# bias_v1.net
KiCad netlist of a schematic drawn in EAGLE
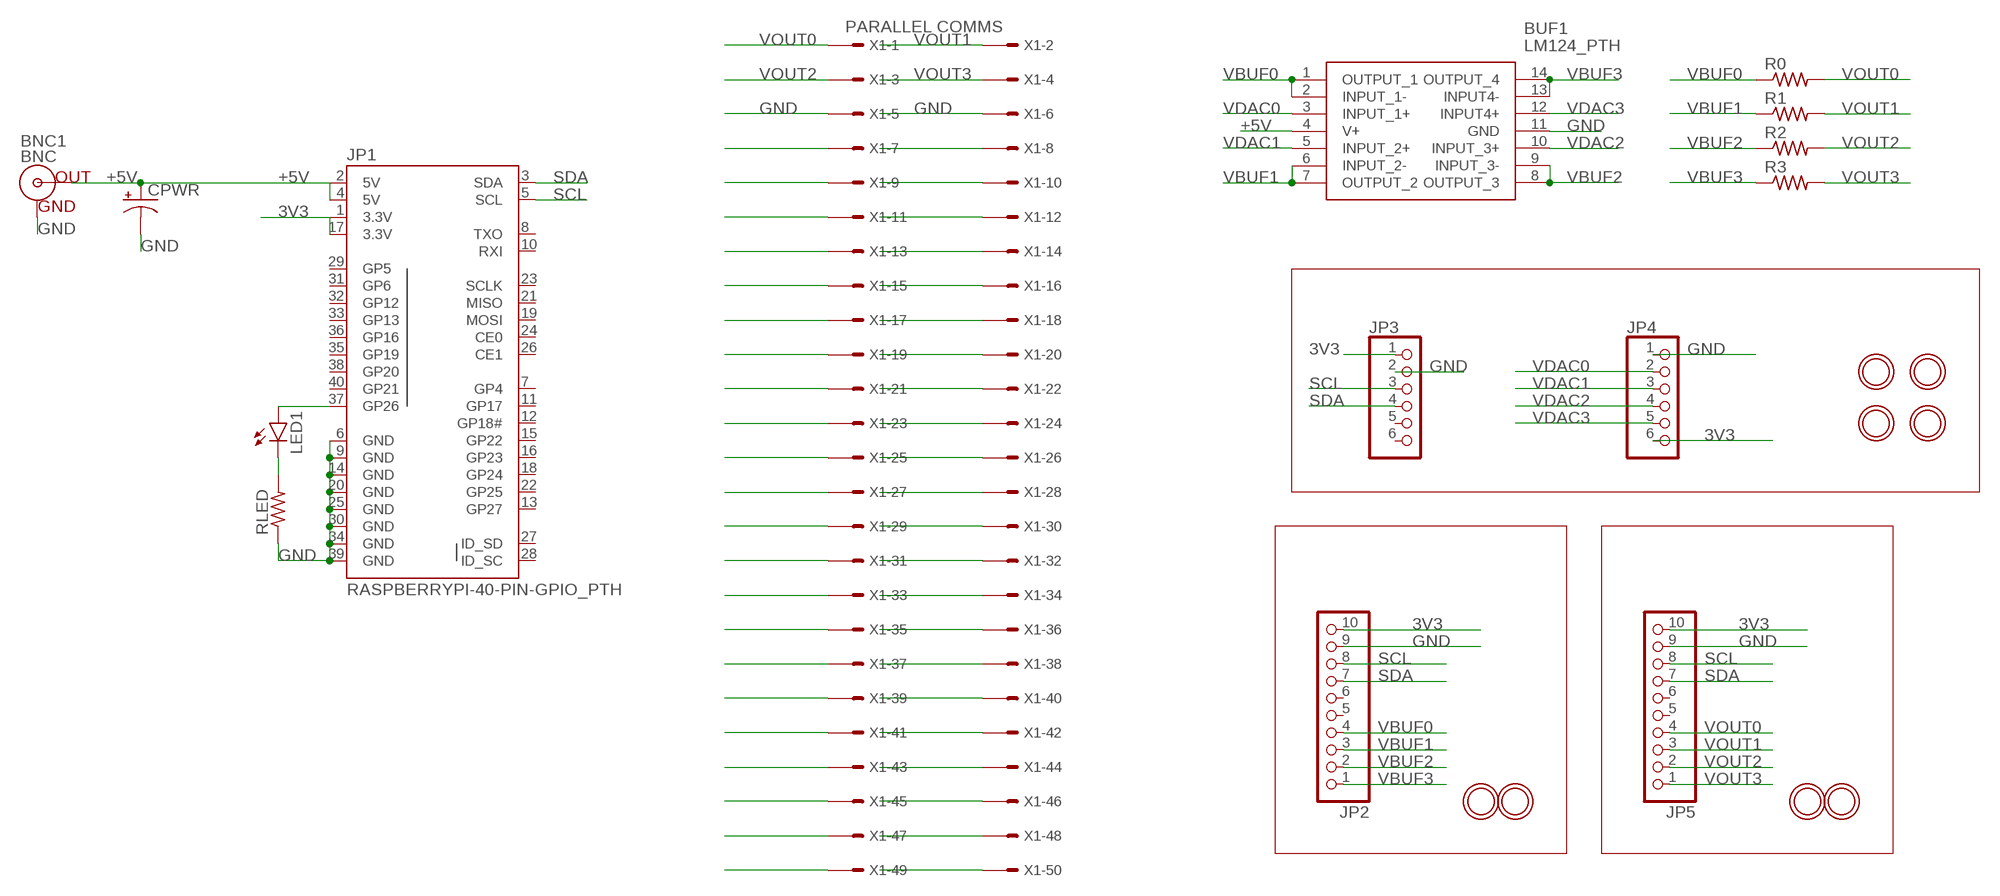
[diagram p0: schematic, sheet 1]

(export (version "E")
  (design (tool "Eeschema 10.0.6"))
  (components
    (comp (ref "BNC1")
      (value "BNC")
      (footprint "eagle-import:BNC")
      (libsource (lib "eagle-import") (part "BNCPTH"))
    )
    (comp (ref "BUF1")
      (value "LM124_PTH")
      (footprint "eagle-import:CDIP790W66P254L1954H508Q14")
      (fields (field (name "ARROW_PART_NUMBER") "LM124J/PB") (field (name "MOUSER_PART_NUMBER") "926-LM124J"))
      (libsource (lib "eagle-import") (part "LM124_PTH"))
    )
    (comp (ref "CPWR")
      (value "CPOL-USE2.5-6")
      (footprint "eagle-import:E2,5-6")
      (libsource (lib "eagle-import") (part "CPOL-USE2.5-6"))
    )
    (comp (ref "JP1")
      (value "RASPBERRYPI-40-PIN-GPIO_PTH")
      (footprint "eagle-import:2X20_SHROUDED")
      (libsource (lib "eagle-import") (part "RASPBERRYPI-40-PIN-GPIO_PTH"))
    )
    (comp (ref "JP2")
      (value "HEADER-1X1070MIL")
      (footprint "eagle-import:1X10_ROUND70")
      (libsource (lib "eagle-import") (part "HEADER-1X1070MIL"))
    )
    (comp (ref "JP3")
      (value "HEADER-1X670MIL")
      (footprint "eagle-import:1X06_ROUND_70")
      (libsource (lib "eagle-import") (part "HEADER-1X670MIL"))
    )
    (comp (ref "JP4")
      (value "HEADER-1X670MIL")
      (footprint "eagle-import:1X06_ROUND_70")
      (libsource (lib "eagle-import") (part "HEADER-1X670MIL"))
    )
    (comp (ref "JP5")
      (value "HEADER-1X1070MIL")
      (footprint "eagle-import:1X10_ROUND70")
      (libsource (lib "eagle-import") (part "HEADER-1X1070MIL"))
    )
    (comp (ref "LED1")
      (value "LED3MM")
      (footprint "eagle-import:LED3MM")
      (libsource (lib "eagle-import") (part "LED3MM"))
    )
    (comp (ref "R0")
      (value "R-US_0204/7")
      (footprint "eagle-import:0204_7")
      (libsource (lib "eagle-import") (part "R-US_0204/7"))
    )
    (comp (ref "R1")
      (value "R-US_0204/7")
      (footprint "eagle-import:0204_7")
      (libsource (lib "eagle-import") (part "R-US_0204/7"))
    )
    (comp (ref "R2")
      (value "R-US_0204/7")
      (footprint "eagle-import:0204_7")
      (libsource (lib "eagle-import") (part "R-US_0204/7"))
    )
    (comp (ref "R3")
      (value "R-US_0204/7")
      (footprint "eagle-import:0204_7")
      (libsource (lib "eagle-import") (part "R-US_0204/7"))
    )
    (comp (ref "RLED")
      (value "R-US_0204/7")
      (footprint "eagle-import:0204_7")
      (libsource (lib "eagle-import") (part "R-US_0204/7"))
    )
    (comp (ref "U$3")
      (value "MOUNTINGHOLE2.5")
      (footprint "eagle-import:MOUNTINGHOLE_2.5_PLATED")
      (libsource (lib "eagle-import") (part "MOUNTINGHOLE2.5"))
    )
    (comp (ref "U$4")
      (value "MOUNTINGHOLE2.5")
      (footprint "eagle-import:MOUNTINGHOLE_2.5_PLATED")
      (libsource (lib "eagle-import") (part "MOUNTINGHOLE2.5"))
    )
    (comp (ref "U$5")
      (value "MOUNTINGHOLE2.5")
      (footprint "eagle-import:MOUNTINGHOLE_2.5_PLATED")
      (libsource (lib "eagle-import") (part "MOUNTINGHOLE2.5"))
    )
    (comp (ref "U$6")
      (value "MOUNTINGHOLE2.5")
      (footprint "eagle-import:MOUNTINGHOLE_2.5_PLATED")
      (libsource (lib "eagle-import") (part "MOUNTINGHOLE2.5"))
    )
    (comp (ref "U$7")
      (value "MOUNTINGHOLE2.5")
      (footprint "eagle-import:MOUNTINGHOLE_2.5_PLATED")
      (libsource (lib "eagle-import") (part "MOUNTINGHOLE2.5"))
    )
    (comp (ref "U$8")
      (value "MOUNTINGHOLE2.5")
      (footprint "eagle-import:MOUNTINGHOLE_2.5_PLATED")
      (libsource (lib "eagle-import") (part "MOUNTINGHOLE2.5"))
    )
    (comp (ref "U$15")
      (value "MOUNTINGHOLE2.5")
      (footprint "eagle-import:MOUNTINGHOLE_2.5_PLATED")
      (libsource (lib "eagle-import") (part "MOUNTINGHOLE2.5"))
    )
    (comp (ref "U$16")
      (value "MOUNTINGHOLE2.5")
      (footprint "eagle-import:MOUNTINGHOLE_2.5_PLATED")
      (libsource (lib "eagle-import") (part "MOUNTINGHOLE2.5"))
    )
    (comp (ref "X1")
      (value "PARALLEL COMMS")
      (footprint "eagle-import:057-050-1")
      (libsource (lib "eagle-import") (part "057-050-1"))
    )
  )
  (nets
    (net (code "1") (name "/+5V") (class "Default")
      (node (ref "BNC1") (pin "S") (pinfunction "OUT_S") (pintype "bidirectional"))
      (node (ref "BUF1") (pin "4") (pinfunction "V+_4") (pintype "bidirectional"))
      (node (ref "CPWR") (pin "+") (pinfunction "+_+") (pintype "passive"))
      (node (ref "JP1") (pin "2") (pinfunction "5V_2") (pintype "power_in"))
      (node (ref "JP1") (pin "4") (pinfunction "5V_4") (pintype "power_in"))
    )
    (net (code "2") (name "/3V3") (class "Default")
      (node (ref "JP1") (pin "1") (pinfunction "3.3V_1") (pintype "power_in"))
      (node (ref "JP1") (pin "17") (pinfunction "3.3V_17") (pintype "power_in"))
      (node (ref "JP2") (pin "10") (pinfunction "10_10") (pintype "passive"))
      (node (ref "JP3") (pin "1") (pinfunction "1_1") (pintype "passive"))
      (node (ref "JP4") (pin "6") (pinfunction "6_6") (pintype "passive"))
      (node (ref "JP5") (pin "10") (pinfunction "10_10") (pintype "passive"))
    )
    (net (code "3") (name "/GND") (class "Default")
      (node (ref "BNC1") (pin "GND") (pinfunction "GND_GND") (pintype "bidirectional"))
      (node (ref "BUF1") (pin "11") (pinfunction "GND_11") (pintype "bidirectional"))
      (node (ref "CPWR") (pin "-") (pinfunction "-_-") (pintype "passive"))
      (node (ref "JP1") (pin "14") (pinfunction "GND_14") (pintype "power_in"))
      (node (ref "JP1") (pin "20") (pinfunction "GND_20") (pintype "power_in"))
      (node (ref "JP1") (pin "25") (pinfunction "GND_25") (pintype "power_in"))
      (node (ref "JP1") (pin "30") (pinfunction "GND_30") (pintype "power_in"))
      (node (ref "JP1") (pin "34") (pinfunction "GND_34") (pintype "power_in"))
      (node (ref "JP1") (pin "39") (pinfunction "GND_39") (pintype "power_in"))
      (node (ref "JP1") (pin "6") (pinfunction "GND_6") (pintype "power_in"))
      (node (ref "JP1") (pin "9") (pinfunction "GND_9") (pintype "power_in"))
      (node (ref "JP2") (pin "9") (pinfunction "9_9") (pintype "passive"))
      (node (ref "JP3") (pin "2") (pinfunction "2_2") (pintype "passive"))
      (node (ref "JP4") (pin "1") (pinfunction "1_1") (pintype "passive"))
      (node (ref "JP5") (pin "9") (pinfunction "9_9") (pintype "passive"))
      (node (ref "RLED") (pin "1") (pinfunction "1_1") (pintype "passive"))
      (node (ref "X1") (pin "5") (pinfunction "S_5") (pintype "passive"))
      (node (ref "X1") (pin "6") (pinfunction "S_6") (pintype "passive"))
    )
    (net (code "4") (name "/SCL") (class "Default")
      (node (ref "JP1") (pin "5") (pinfunction "SCL_5") (pintype "bidirectional"))
      (node (ref "JP2") (pin "8") (pinfunction "8_8") (pintype "passive"))
      (node (ref "JP3") (pin "3") (pinfunction "3_3") (pintype "passive"))
      (node (ref "JP5") (pin "8") (pinfunction "8_8") (pintype "passive"))
    )
    (net (code "5") (name "/SDA") (class "Default")
      (node (ref "JP1") (pin "3") (pinfunction "SDA_3") (pintype "bidirectional"))
      (node (ref "JP2") (pin "7") (pinfunction "7_7") (pintype "passive"))
      (node (ref "JP3") (pin "4") (pinfunction "4_4") (pintype "passive"))
      (node (ref "JP5") (pin "7") (pinfunction "7_7") (pintype "passive"))
    )
    (net (code "6") (name "/VBUF0") (class "Default")
      (node (ref "BUF1") (pin "1") (pinfunction "OUTPUT_1_1") (pintype "bidirectional"))
      (node (ref "BUF1") (pin "2") (pinfunction "INPUT_1-_2") (pintype "bidirectional"))
      (node (ref "JP2") (pin "4") (pinfunction "4_4") (pintype "passive"))
      (node (ref "R0") (pin "1") (pinfunction "1_1") (pintype "passive"))
    )
    (net (code "7") (name "/VBUF1") (class "Default")
      (node (ref "BUF1") (pin "6") (pinfunction "INPUT_2-_6") (pintype "bidirectional"))
      (node (ref "BUF1") (pin "7") (pinfunction "OUTPUT_2_7") (pintype "bidirectional"))
      (node (ref "JP2") (pin "3") (pinfunction "3_3") (pintype "passive"))
      (node (ref "R1") (pin "1") (pinfunction "1_1") (pintype "passive"))
    )
    (net (code "8") (name "/VBUF2") (class "Default")
      (node (ref "BUF1") (pin "8") (pinfunction "OUTPUT_3_8") (pintype "bidirectional"))
      (node (ref "BUF1") (pin "9") (pinfunction "INPUT_3-_9") (pintype "bidirectional"))
      (node (ref "JP2") (pin "2") (pinfunction "2_2") (pintype "passive"))
      (node (ref "R2") (pin "1") (pinfunction "1_1") (pintype "passive"))
    )
    (net (code "9") (name "/VBUF3") (class "Default")
      (node (ref "BUF1") (pin "13") (pinfunction "INPUT4-_13") (pintype "bidirectional"))
      (node (ref "BUF1") (pin "14") (pinfunction "OUTPUT_4_14") (pintype "bidirectional"))
      (node (ref "JP2") (pin "1") (pinfunction "1_1") (pintype "passive"))
      (node (ref "R3") (pin "1") (pinfunction "1_1") (pintype "passive"))
    )
    (net (code "10") (name "/VDAC0") (class "Default")
      (node (ref "BUF1") (pin "3") (pinfunction "INPUT_1+_3") (pintype "bidirectional"))
      (node (ref "JP4") (pin "2") (pinfunction "2_2") (pintype "passive"))
    )
    (net (code "11") (name "/VDAC1") (class "Default")
      (node (ref "BUF1") (pin "5") (pinfunction "INPUT_2+_5") (pintype "bidirectional"))
      (node (ref "JP4") (pin "3") (pinfunction "3_3") (pintype "passive"))
    )
    (net (code "12") (name "/VDAC2") (class "Default")
      (node (ref "BUF1") (pin "10") (pinfunction "INPUT_3+_10") (pintype "bidirectional"))
      (node (ref "JP4") (pin "4") (pinfunction "4_4") (pintype "passive"))
    )
    (net (code "13") (name "/VDAC3") (class "Default")
      (node (ref "BUF1") (pin "12") (pinfunction "INPUT4+_12") (pintype "bidirectional"))
      (node (ref "JP4") (pin "5") (pinfunction "5_5") (pintype "passive"))
    )
    (net (code "14") (name "/VOUT0") (class "Default")
      (node (ref "JP5") (pin "4") (pinfunction "4_4") (pintype "passive"))
      (node (ref "R0") (pin "2") (pinfunction "2_2") (pintype "passive"))
      (node (ref "X1") (pin "1") (pinfunction "S_1") (pintype "passive"))
    )
    (net (code "15") (name "/VOUT1") (class "Default")
      (node (ref "JP5") (pin "3") (pinfunction "3_3") (pintype "passive"))
      (node (ref "R1") (pin "2") (pinfunction "2_2") (pintype "passive"))
      (node (ref "X1") (pin "2") (pinfunction "S_2") (pintype "passive"))
    )
    (net (code "16") (name "/VOUT2") (class "Default")
      (node (ref "JP5") (pin "2") (pinfunction "2_2") (pintype "passive"))
      (node (ref "R2") (pin "2") (pinfunction "2_2") (pintype "passive"))
      (node (ref "X1") (pin "3") (pinfunction "S_3") (pintype "passive"))
    )
    (net (code "17") (name "/VOUT3") (class "Default")
      (node (ref "JP5") (pin "1") (pinfunction "1_1") (pintype "passive"))
      (node (ref "R3") (pin "2") (pinfunction "2_2") (pintype "passive"))
      (node (ref "X1") (pin "4") (pinfunction "S_4") (pintype "passive"))
    )
    (net (code "18") (name "Net-(JP1-GP26)") (class "Default")
      (node (ref "JP1") (pin "37") (pinfunction "GP26_37") (pintype "bidirectional"))
      (node (ref "LED1") (pin "A") (pinfunction "A_A") (pintype "passive"))
    )
    (net (code "19") (name "Net-(LED1-C)") (class "Default")
      (node (ref "LED1") (pin "K") (pinfunction "C_K") (pintype "passive"))
      (node (ref "RLED") (pin "2") (pinfunction "2_2") (pintype "passive"))
    )
    (net (code "20") (name "unconnected-(JP1-CE0-Pad24)") (class "Default")
      (node (ref "JP1") (pin "24") (pinfunction "CE0_24") (pintype "output"))
    )
    (net (code "21") (name "unconnected-(JP1-CE1-Pad26)") (class "Default")
      (node (ref "JP1") (pin "26") (pinfunction "CE1_26") (pintype "output"))
    )
    (net (code "22") (name "unconnected-(JP1-GP4-Pad7)") (class "Default")
      (node (ref "JP1") (pin "7") (pinfunction "GP4_7") (pintype "bidirectional"))
    )
    (net (code "23") (name "unconnected-(JP1-GP5-Pad29)") (class "Default")
      (node (ref "JP1") (pin "29") (pinfunction "GP5_29") (pintype "bidirectional"))
    )
    (net (code "24") (name "unconnected-(JP1-GP6-Pad31)") (class "Default")
      (node (ref "JP1") (pin "31") (pinfunction "GP6_31") (pintype "bidirectional"))
    )
    (net (code "25") (name "unconnected-(JP1-GP12-Pad32)") (class "Default")
      (node (ref "JP1") (pin "32") (pinfunction "GP12_32") (pintype "bidirectional"))
    )
    (net (code "26") (name "unconnected-(JP1-GP13-Pad33)") (class "Default")
      (node (ref "JP1") (pin "33") (pinfunction "GP13_33") (pintype "bidirectional"))
    )
    (net (code "27") (name "unconnected-(JP1-GP16-Pad36)") (class "Default")
      (node (ref "JP1") (pin "36") (pinfunction "GP16_36") (pintype "bidirectional"))
    )
    (net (code "28") (name "unconnected-(JP1-GP17-Pad11)") (class "Default")
      (node (ref "JP1") (pin "11") (pinfunction "GP17_11") (pintype "bidirectional"))
    )
    (net (code "29") (name "unconnected-(JP1-GP18#-Pad12)") (class "Default")
      (node (ref "JP1") (pin "12") (pinfunction "GP18#_12") (pintype "bidirectional"))
    )
    (net (code "30") (name "unconnected-(JP1-GP19-Pad35)") (class "Default")
      (node (ref "JP1") (pin "35") (pinfunction "GP19_35") (pintype "bidirectional"))
    )
    (net (code "31") (name "unconnected-(JP1-GP20-Pad38)") (class "Default")
      (node (ref "JP1") (pin "38") (pinfunction "GP20_38") (pintype "bidirectional"))
    )
    (net (code "32") (name "unconnected-(JP1-GP21-Pad40)") (class "Default")
      (node (ref "JP1") (pin "40") (pinfunction "GP21_40") (pintype "bidirectional"))
    )
    (net (code "33") (name "unconnected-(JP1-GP22-Pad15)") (class "Default")
      (node (ref "JP1") (pin "15") (pinfunction "GP22_15") (pintype "bidirectional"))
    )
    (net (code "34") (name "unconnected-(JP1-GP23-Pad16)") (class "Default")
      (node (ref "JP1") (pin "16") (pinfunction "GP23_16") (pintype "bidirectional"))
    )
    (net (code "35") (name "unconnected-(JP1-GP24-Pad18)") (class "Default")
      (node (ref "JP1") (pin "18") (pinfunction "GP24_18") (pintype "bidirectional"))
    )
    (net (code "36") (name "unconnected-(JP1-GP25-Pad22)") (class "Default")
      (node (ref "JP1") (pin "22") (pinfunction "GP25_22") (pintype "bidirectional"))
    )
    (net (code "37") (name "unconnected-(JP1-GP27-Pad13)") (class "Default")
      (node (ref "JP1") (pin "13") (pinfunction "GP27_13") (pintype "bidirectional"))
    )
    (net (code "38") (name "unconnected-(JP1-ID_SC-Pad28)") (class "Default")
      (node (ref "JP1") (pin "28") (pinfunction "ID_SC_28") (pintype "bidirectional"))
    )
    (net (code "39") (name "unconnected-(JP1-ID_SD-Pad27)") (class "Default")
      (node (ref "JP1") (pin "27") (pinfunction "ID_SD_27") (pintype "bidirectional"))
    )
    (net (code "40") (name "unconnected-(JP1-MISO-Pad21)") (class "Default")
      (node (ref "JP1") (pin "21") (pinfunction "MISO_21") (pintype "input"))
    )
    (net (code "41") (name "unconnected-(JP1-MOSI-Pad19)") (class "Default")
      (node (ref "JP1") (pin "19") (pinfunction "MOSI_19") (pintype "output"))
    )
    (net (code "42") (name "unconnected-(JP1-RXI-Pad10)") (class "Default")
      (node (ref "JP1") (pin "10") (pinfunction "RXI_10") (pintype "input"))
    )
    (net (code "43") (name "unconnected-(JP1-SCLK-Pad23)") (class "Default")
      (node (ref "JP1") (pin "23") (pinfunction "SCLK_23") (pintype "output"))
    )
    (net (code "44") (name "unconnected-(JP1-TXO-Pad8)") (class "Default")
      (node (ref "JP1") (pin "8") (pinfunction "TXO_8") (pintype "output"))
    )
    (net (code "45") (name "unconnected-(JP2-Pad5)") (class "Default")
      (node (ref "JP2") (pin "5") (pinfunction "5_5") (pintype "passive"))
    )
    (net (code "46") (name "unconnected-(JP2-Pad6)") (class "Default")
      (node (ref "JP2") (pin "6") (pinfunction "6_6") (pintype "passive"))
    )
    (net (code "47") (name "unconnected-(JP3-Pad5)") (class "Default")
      (node (ref "JP3") (pin "5") (pinfunction "5_5") (pintype "passive"))
    )
    (net (code "48") (name "unconnected-(JP3-Pad6)") (class "Default")
      (node (ref "JP3") (pin "6") (pinfunction "6_6") (pintype "passive"))
    )
    (net (code "49") (name "unconnected-(JP5-Pad5)") (class "Default")
      (node (ref "JP5") (pin "5") (pinfunction "5_5") (pintype "passive"))
    )
    (net (code "50") (name "unconnected-(JP5-Pad6)") (class "Default")
      (node (ref "JP5") (pin "6") (pinfunction "6_6") (pintype "passive"))
    )
    (net (code "51") (name "unconnected-(X1AA-S-Pad33)") (class "Default")
      (node (ref "X1") (pin "33") (pinfunction "S_33") (pintype "passive"))
    )
    (net (code "52") (name "unconnected-(X1AB-S-Pad34)") (class "Default")
      (node (ref "X1") (pin "34") (pinfunction "S_34") (pintype "passive"))
    )
    (net (code "53") (name "unconnected-(X1AC-S-Pad35)") (class "Default")
      (node (ref "X1") (pin "35") (pinfunction "S_35") (pintype "passive"))
    )
    (net (code "54") (name "unconnected-(X1AD-S-Pad36)") (class "Default")
      (node (ref "X1") (pin "36") (pinfunction "S_36") (pintype "passive"))
    )
    (net (code "55") (name "unconnected-(X1AE-S-Pad37)") (class "Default")
      (node (ref "X1") (pin "37") (pinfunction "S_37") (pintype "passive"))
    )
    (net (code "56") (name "unconnected-(X1AF-S-Pad38)") (class "Default")
      (node (ref "X1") (pin "38") (pinfunction "S_38") (pintype "passive"))
    )
    (net (code "57") (name "unconnected-(X1AG-S-Pad39)") (class "Default")
      (node (ref "X1") (pin "39") (pinfunction "S_39") (pintype "passive"))
    )
    (net (code "58") (name "unconnected-(X1AI-S-Pad40)") (class "Default")
      (node (ref "X1") (pin "40") (pinfunction "S_40") (pintype "passive"))
    )
    (net (code "59") (name "unconnected-(X1AJ-S-Pad41)") (class "Default")
      (node (ref "X1") (pin "41") (pinfunction "S_41") (pintype "passive"))
    )
    (net (code "60") (name "unconnected-(X1AK-S-Pad42)") (class "Default")
      (node (ref "X1") (pin "42") (pinfunction "S_42") (pintype "passive"))
    )
    (net (code "61") (name "unconnected-(X1AL-S-Pad43)") (class "Default")
      (node (ref "X1") (pin "43") (pinfunction "S_43") (pintype "passive"))
    )
    (net (code "62") (name "unconnected-(X1AM-S-Pad44)") (class "Default")
      (node (ref "X1") (pin "44") (pinfunction "S_44") (pintype "passive"))
    )
    (net (code "63") (name "unconnected-(X1AN-S-Pad45)") (class "Default")
      (node (ref "X1") (pin "45") (pinfunction "S_45") (pintype "passive"))
    )
    (net (code "64") (name "unconnected-(X1AO-S-Pad46)") (class "Default")
      (node (ref "X1") (pin "46") (pinfunction "S_46") (pintype "passive"))
    )
    (net (code "65") (name "unconnected-(X1AP-S-Pad47)") (class "Default")
      (node (ref "X1") (pin "47") (pinfunction "S_47") (pintype "passive"))
    )
    (net (code "66") (name "unconnected-(X1AQ-S-Pad48)") (class "Default")
      (node (ref "X1") (pin "48") (pinfunction "S_48") (pintype "passive"))
    )
    (net (code "67") (name "unconnected-(X1AR-S-Pad49)") (class "Default")
      (node (ref "X1") (pin "49") (pinfunction "S_49") (pintype "passive"))
    )
    (net (code "68") (name "unconnected-(X1AT-S-Pad50)") (class "Default")
      (node (ref "X1") (pin "50") (pinfunction "S_50") (pintype "passive"))
    )
    (net (code "69") (name "unconnected-(X1AV-S-Pad7)") (class "Default")
      (node (ref "X1") (pin "7") (pinfunction "S_7") (pintype "passive"))
    )
    (net (code "70") (name "unconnected-(X1AW-S-Pad8)") (class "Default")
      (node (ref "X1") (pin "8") (pinfunction "S_8") (pintype "passive"))
    )
    (net (code "71") (name "unconnected-(X1AX-S-Pad9)") (class "Default")
      (node (ref "X1") (pin "9") (pinfunction "S_9") (pintype "passive"))
    )
    (net (code "72") (name "unconnected-(X1B-S-Pad10)") (class "Default")
      (node (ref "X1") (pin "10") (pinfunction "S_10") (pintype "passive"))
    )
    (net (code "73") (name "unconnected-(X1C-S-Pad11)") (class "Default")
      (node (ref "X1") (pin "11") (pinfunction "S_11") (pintype "passive"))
    )
    (net (code "74") (name "unconnected-(X1D-S-Pad12)") (class "Default")
      (node (ref "X1") (pin "12") (pinfunction "S_12") (pintype "passive"))
    )
    (net (code "75") (name "unconnected-(X1E-S-Pad13)") (class "Default")
      (node (ref "X1") (pin "13") (pinfunction "S_13") (pintype "passive"))
    )
    (net (code "76") (name "unconnected-(X1F-S-Pad14)") (class "Default")
      (node (ref "X1") (pin "14") (pinfunction "S_14") (pintype "passive"))
    )
    (net (code "77") (name "unconnected-(X1G-S-Pad15)") (class "Default")
      (node (ref "X1") (pin "15") (pinfunction "S_15") (pintype "passive"))
    )
    (net (code "78") (name "unconnected-(X1H-S-Pad16)") (class "Default")
      (node (ref "X1") (pin "16") (pinfunction "S_16") (pintype "passive"))
    )
    (net (code "79") (name "unconnected-(X1I-S-Pad17)") (class "Default")
      (node (ref "X1") (pin "17") (pinfunction "S_17") (pintype "passive"))
    )
    (net (code "80") (name "unconnected-(X1J-S-Pad18)") (class "Default")
      (node (ref "X1") (pin "18") (pinfunction "S_18") (pintype "passive"))
    )
    (net (code "81") (name "unconnected-(X1K-S-Pad19)") (class "Default")
      (node (ref "X1") (pin "19") (pinfunction "S_19") (pintype "passive"))
    )
    (net (code "82") (name "unconnected-(X1M-S-Pad20)") (class "Default")
      (node (ref "X1") (pin "20") (pinfunction "S_20") (pintype "passive"))
    )
    (net (code "83") (name "unconnected-(X1N-S-Pad21)") (class "Default")
      (node (ref "X1") (pin "21") (pinfunction "S_21") (pintype "passive"))
    )
    (net (code "84") (name "unconnected-(X1O-S-Pad22)") (class "Default")
      (node (ref "X1") (pin "22") (pinfunction "S_22") (pintype "passive"))
    )
    (net (code "85") (name "unconnected-(X1P-S-Pad23)") (class "Default")
      (node (ref "X1") (pin "23") (pinfunction "S_23") (pintype "passive"))
    )
    (net (code "86") (name "unconnected-(X1Q-S-Pad24)") (class "Default")
      (node (ref "X1") (pin "24") (pinfunction "S_24") (pintype "passive"))
    )
    (net (code "87") (name "unconnected-(X1R-S-Pad25)") (class "Default")
      (node (ref "X1") (pin "25") (pinfunction "S_25") (pintype "passive"))
    )
    (net (code "88") (name "unconnected-(X1S-S-Pad26)") (class "Default")
      (node (ref "X1") (pin "26") (pinfunction "S_26") (pintype "passive"))
    )
    (net (code "89") (name "unconnected-(X1T-S-Pad27)") (class "Default")
      (node (ref "X1") (pin "27") (pinfunction "S_27") (pintype "passive"))
    )
    (net (code "90") (name "unconnected-(X1U-S-Pad28)") (class "Default")
      (node (ref "X1") (pin "28") (pinfunction "S_28") (pintype "passive"))
    )
    (net (code "91") (name "unconnected-(X1V-S-Pad29)") (class "Default")
      (node (ref "X1") (pin "29") (pinfunction "S_29") (pintype "passive"))
    )
    (net (code "92") (name "unconnected-(X1X-S-Pad30)") (class "Default")
      (node (ref "X1") (pin "30") (pinfunction "S_30") (pintype "passive"))
    )
    (net (code "93") (name "unconnected-(X1Y-S-Pad31)") (class "Default")
      (node (ref "X1") (pin "31") (pinfunction "S_31") (pintype "passive"))
    )
    (net (code "94") (name "unconnected-(X1Z-S-Pad32)") (class "Default")
      (node (ref "X1") (pin "32") (pinfunction "S_32") (pintype "passive"))
    )
  )
)
